# ToolTron_RFIDBoxv2_0.net
KiCad netlist of a schematic drawn in EAGLE
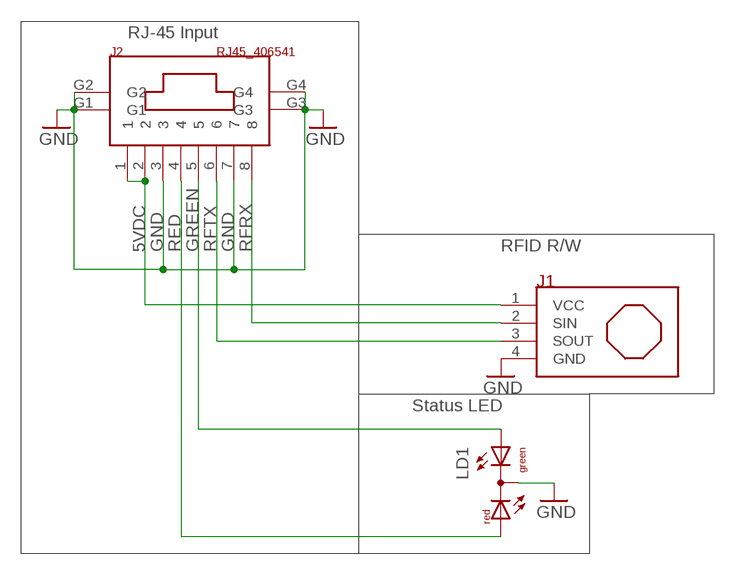
[diagram p0: schematic, sheet 1]

(export (version "E")
  (design (tool "Eeschema 10.0.6"))
  (components
    (comp (ref "J1")
      (value "RFID_SERIAL_R/W")
      (footprint "eagle-import:1X4_HEADER")
      (libsource (lib "eagle-import") (part "RFID_SERIAL_R/W"))
    )
    (comp (ref "J2")
      (value "RJ45_406541")
      (footprint "eagle-import:1-406541-1")
      (libsource (lib "eagle-import") (part "RJ45_406541"))
    )
    (comp (ref "LD1")
      (value "DUOLED-RG-C")
      (footprint "eagle-import:DUOLED-C-5MM")
      (libsource (lib "eagle-import") (part "DUOLED-RG-C"))
    )
  )
  (nets
    (net (code "1") (name "/5VDC") (class "Default")
      (node (ref "J1") (pin "1") (pinfunction "VCC_1") (pintype "bidirectional"))
      (node (ref "J2") (pin "1") (pinfunction "1_1") (pintype "bidirectional"))
      (node (ref "J2") (pin "2") (pinfunction "2_2") (pintype "bidirectional"))
    )
    (net (code "2") (name "/GREEN") (class "Default")
      (node (ref "J2") (pin "5") (pinfunction "5_5") (pintype "bidirectional"))
      (node (ref "LD1") (pin "AX") (pinfunction "AG_AX") (pintype "passive"))
    )
    (net (code "3") (name "/RED") (class "Default")
      (node (ref "J2") (pin "4") (pinfunction "4_4") (pintype "bidirectional"))
      (node (ref "LD1") (pin "AR") (pinfunction "AR_AR") (pintype "passive"))
    )
    (net (code "4") (name "/RFRX") (class "Default")
      (node (ref "J1") (pin "2") (pinfunction "SIN_2") (pintype "bidirectional"))
      (node (ref "J2") (pin "8") (pinfunction "8_8") (pintype "bidirectional"))
    )
    (net (code "5") (name "/RFTX") (class "Default")
      (node (ref "J1") (pin "3") (pinfunction "SOUT_3") (pintype "bidirectional"))
      (node (ref "J2") (pin "6") (pinfunction "6_6") (pintype "bidirectional"))
    )
    (net (code "6") (name "GND") (class "Default")
      (node (ref "J1") (pin "4") (pinfunction "GND_4") (pintype "bidirectional"))
      (node (ref "J2") (pin "3") (pinfunction "3_3") (pintype "bidirectional"))
      (node (ref "J2") (pin "7") (pinfunction "7_7") (pintype "bidirectional"))
      (node (ref "J2") (pin "G1") (pinfunction "G1_G1") (pintype "bidirectional"))
      (node (ref "J2") (pin "G2") (pinfunction "G2_G2") (pintype "bidirectional"))
      (node (ref "J2") (pin "G3") (pinfunction "G3_G3") (pintype "bidirectional"))
      (node (ref "J2") (pin "G4") (pinfunction "G4_G4") (pintype "bidirectional"))
      (node (ref "LD1") (pin "C") (pinfunction "C_C") (pintype "passive"))
    )
  )
)
